# thinMan.net
KiCad netlist of a schematic drawn in EAGLE
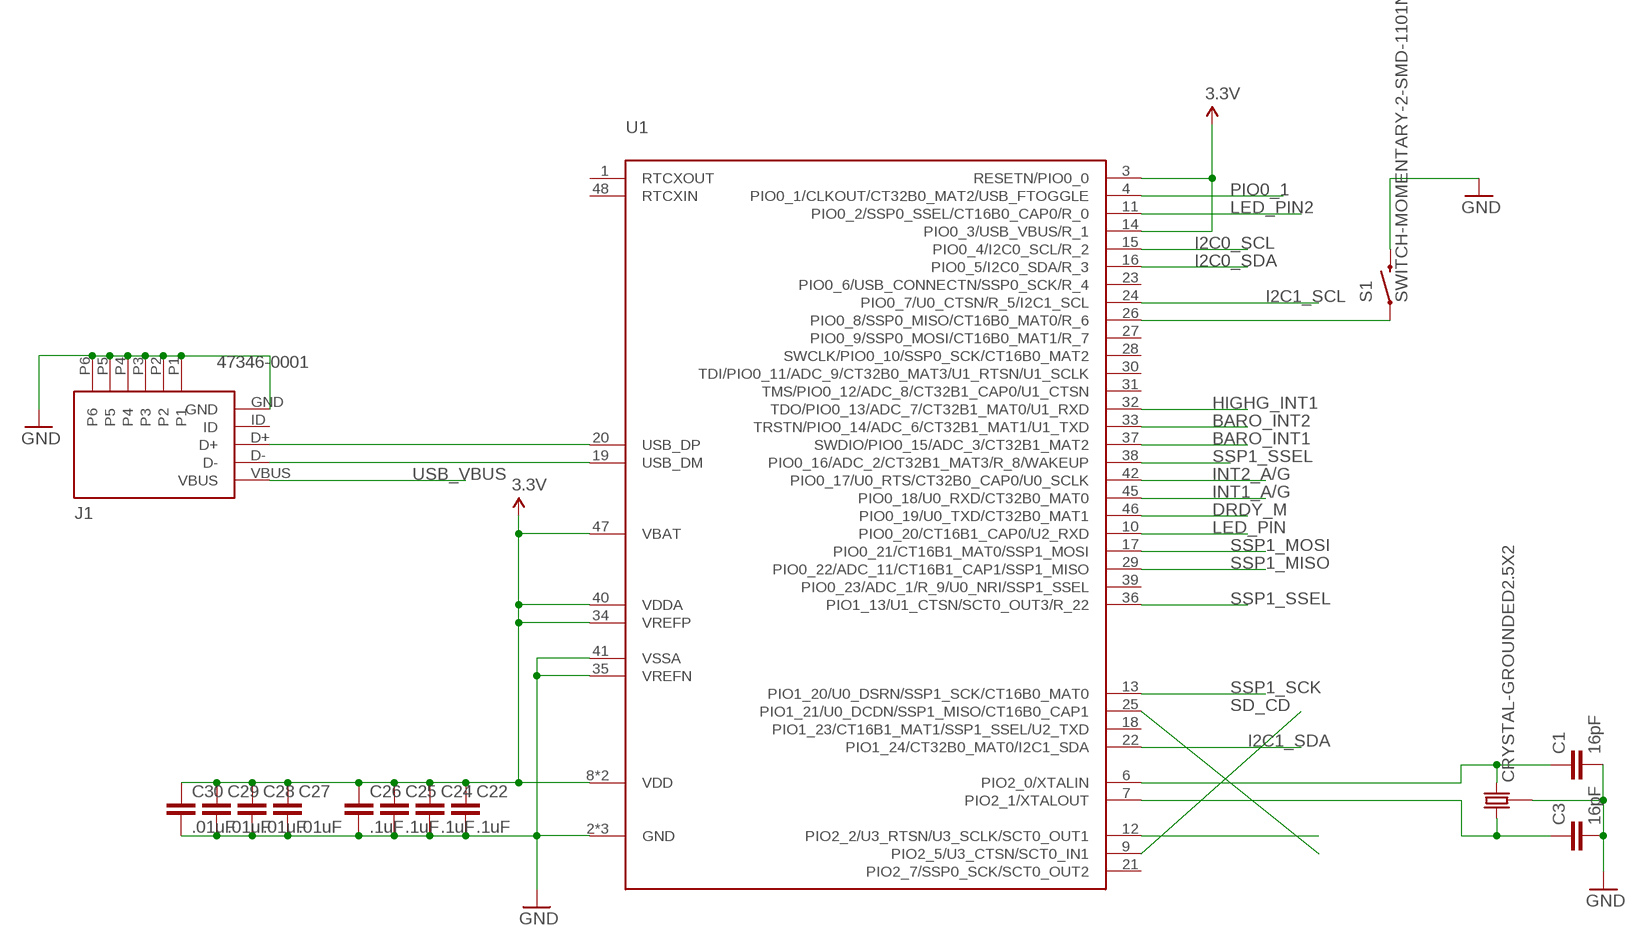
[diagram p0: schematic, sheet 1]
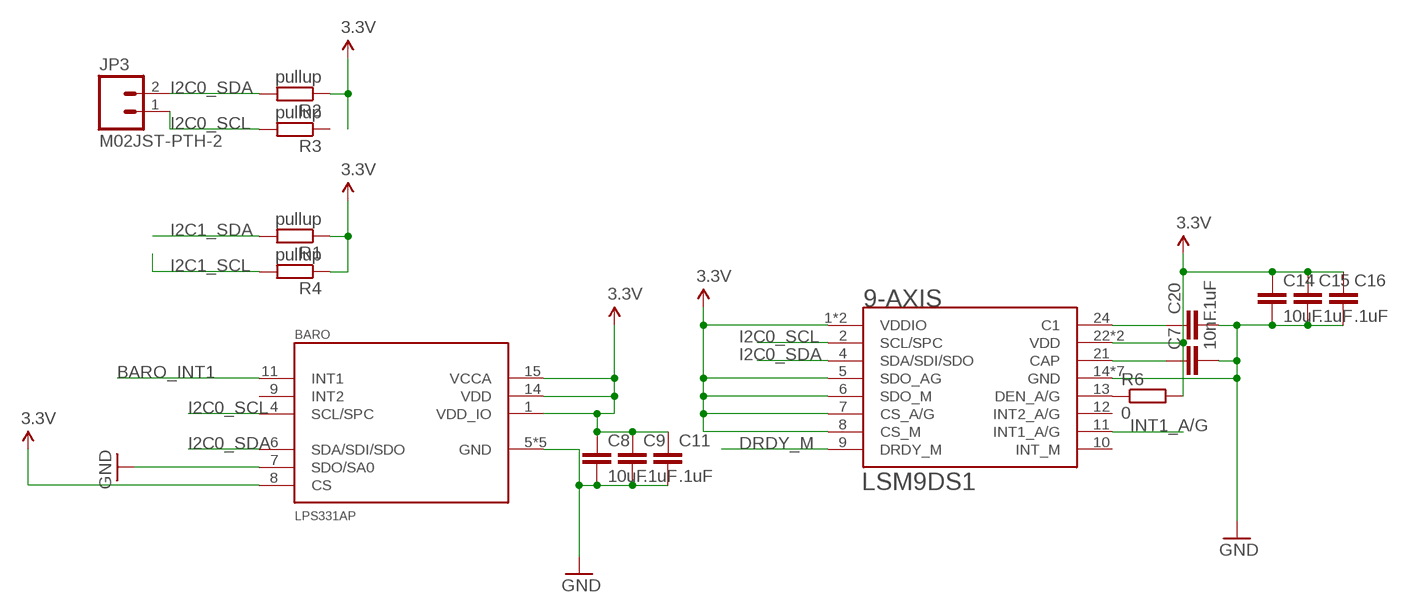
[diagram p1: schematic, sheet 2]
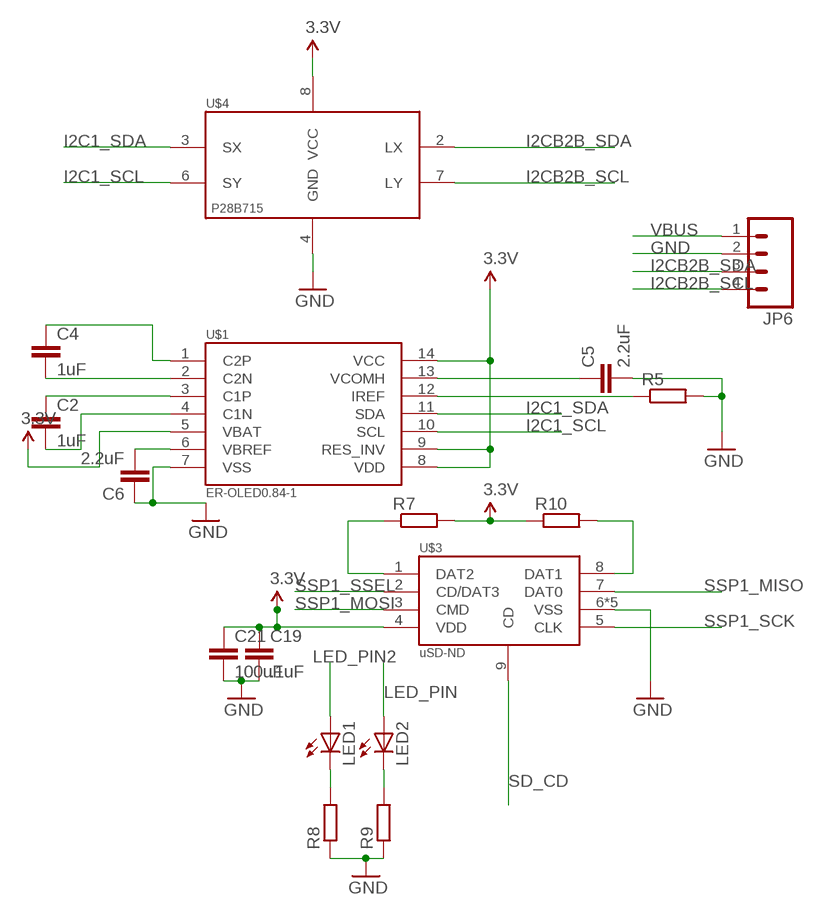
[diagram p2: schematic, sheet 3]
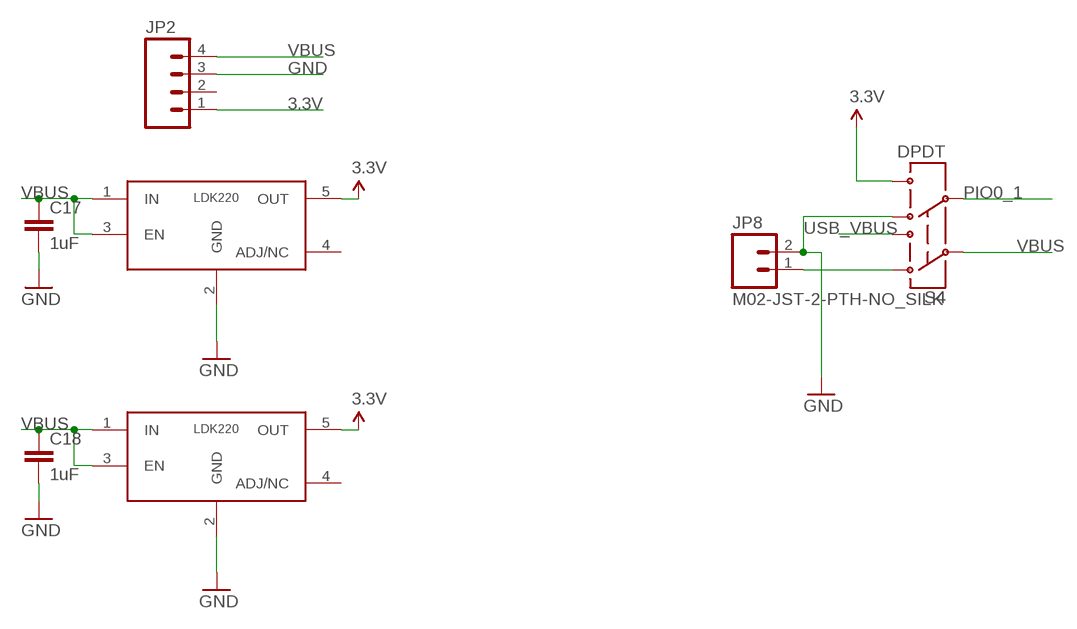
[diagram p3: schematic, sheet 4]

(export (version "E")
  (design (tool "Eeschema 10.0.6"))
  (components
    (comp (ref "C17")
      (value "1uF")
      (footprint "eagle-import:C0402")
      (libsource (lib "eagle-import") (part "C0402"))
    )
    (comp (ref "C18")
      (value "1uF")
      (footprint "eagle-import:C0402")
      (libsource (lib "eagle-import") (part "C0402"))
    )
    (comp (ref "JP2")
      (value "M04JST")
      (footprint "eagle-import:1X04-1.5MM_JST")
      (libsource (lib "eagle-import") (part "M04JST"))
    )
    (comp (ref "JP8")
      (value "M02-JST-2-PTH-NO_SILK")
      (footprint "eagle-import:JST-2-PTH-NS")
      (libsource (lib "eagle-import") (part "M02-JST-2-PTH-NO_SILK"))
    )
    (comp (ref "S4")
      (value "DPDT")
      (footprint "eagle-import:AYZ0202")
      (libsource (lib "eagle-import") (part "SWITCH-DPDTAYZ0202"))
    )
    (comp (ref "U$2")
      (value "LDK220M33R")
      (footprint "eagle-import:SOT23-5")
      (libsource (lib "eagle-import") (part "LDK220M33R"))
    )
    (comp (ref "U$6")
      (value "LDK220M33R")
      (footprint "eagle-import:SOT23-5")
      (libsource (lib "eagle-import") (part "LDK220M33R"))
    )
    (comp (ref "9-AXIS")
      (value "LSM9DS1")
      (footprint "eagle-import:LGA-24L-3.5X3X1")
      (libsource (lib "eagle-import") (part "LSM9DS1"))
    )
    (comp (ref "BARO")
      (value "LPS331AP")
      (footprint "eagle-import:LGA-16-3X3X1")
      (fields (field (name "MPN") "LPS331APTR"))
      (libsource (lib "eagle-import") (part "LPS331AP"))
    )
    (comp (ref "C7")
      (value "10nF")
      (footprint "eagle-import:C0402")
      (fields (field (name "MPN") "S103M47Z5UN63L0R"))
      (libsource (lib "eagle-import") (part "C0402"))
    )
    (comp (ref "C8")
      (value "10uF")
      (footprint "eagle-import:C0402")
      (libsource (lib "eagle-import") (part "C0402"))
    )
    (comp (ref "C9")
      (value ".1uF")
      (footprint "eagle-import:C0402")
      (libsource (lib "eagle-import") (part "C0402"))
    )
    (comp (ref "C11")
      (value ".1uF")
      (footprint "eagle-import:C0402")
      (libsource (lib "eagle-import") (part "C0402"))
    )
    (comp (ref "C14")
      (value "10uF")
      (footprint "eagle-import:C0402")
      (libsource (lib "eagle-import") (part "C0402"))
    )
    (comp (ref "C15")
      (value ".1uF")
      (footprint "eagle-import:C0402")
      (libsource (lib "eagle-import") (part "C0402"))
    )
    (comp (ref "C16")
      (value ".1uF")
      (footprint "eagle-import:C0402")
      (libsource (lib "eagle-import") (part "C0402"))
    )
    (comp (ref "C20")
      (value ".1uF")
      (footprint "eagle-import:C0402")
      (fields (field (name "MPN") "S103M47Z5UN63L0R"))
      (libsource (lib "eagle-import") (part "C0402"))
    )
    (comp (ref "JP3")
      (value "M02JST-PTH-2")
      (footprint "eagle-import:JST-2-PTH")
      (libsource (lib "eagle-import") (part "M02JST-PTH-2"))
    )
    (comp (ref "R1")
      (value "pullup")
      (footprint "eagle-import:R0805")
      (libsource (lib "eagle-import") (part "R0805"))
    )
    (comp (ref "R2")
      (value "pullup")
      (footprint "eagle-import:R0402")
      (libsource (lib "eagle-import") (part "R0402"))
    )
    (comp (ref "R3")
      (value "pullup")
      (footprint "eagle-import:R0402")
      (libsource (lib "eagle-import") (part "R0402"))
    )
    (comp (ref "R4")
      (value "pullup")
      (footprint "eagle-import:R0805")
      (libsource (lib "eagle-import") (part "R0805"))
    )
    (comp (ref "R6")
      (value "0")
      (footprint "eagle-import:R0402")
      (libsource (lib "eagle-import") (part "R0402"))
    )
    (comp (ref "C2")
      (value "1uF")
      (footprint "eagle-import:C0402")
      (fields (field (name "MPN") "MC0402X105M6R3CT"))
      (libsource (lib "eagle-import") (part "C0402"))
    )
    (comp (ref "C4")
      (value "1uF")
      (footprint "eagle-import:C0402")
      (fields (field (name "MPN") "MC0402X105M6R3CT"))
      (libsource (lib "eagle-import") (part "C0402"))
    )
    (comp (ref "C5")
      (value "2.2uF")
      (footprint "eagle-import:C0402")
      (fields (field (name "MPN") "C1005X6S0G225M050BC"))
      (libsource (lib "eagle-import") (part "C0402"))
    )
    (comp (ref "C6")
      (value "2.2uF")
      (footprint "eagle-import:C0402")
      (fields (field (name "MPN") "C1005X6S0G225M050BC"))
      (libsource (lib "eagle-import") (part "C0402"))
    )
    (comp (ref "C19")
      (value ".1uF")
      (footprint "eagle-import:C0402")
      (libsource (lib "eagle-import") (part "C0402"))
    )
    (comp (ref "C21")
      (value "100uF")
      (footprint "eagle-import:C1206")
      (libsource (lib "eagle-import") (part "CC1206"))
    )
    (comp (ref "JP6")
      (value "M04JST")
      (footprint "eagle-import:1X04-1.5MM_JST")
      (libsource (lib "eagle-import") (part "M04JST"))
    )
    (comp (ref "LED1")
      (value "LEDCHIPLED_0603")
      (footprint "eagle-import:CHIPLED_0603")
      (libsource (lib "eagle-import") (part "LEDCHIPLED_0603"))
    )
    (comp (ref "LED2")
      (value "LEDCHIPLED_0603")
      (footprint "eagle-import:CHIPLED_0603")
      (libsource (lib "eagle-import") (part "LEDCHIPLED_0603"))
    )
    (comp (ref "R5")
      (value "R0402")
      (footprint "eagle-import:R0402")
      (libsource (lib "eagle-import") (part "R0402"))
    )
    (comp (ref "R7")
      (value "R0402")
      (footprint "eagle-import:R0402")
      (libsource (lib "eagle-import") (part "R0402"))
    )
    (comp (ref "R8")
      (value "R0402")
      (footprint "eagle-import:R0402")
      (libsource (lib "eagle-import") (part "R0402"))
    )
    (comp (ref "R9")
      (value "R0402")
      (footprint "eagle-import:R0402")
      (libsource (lib "eagle-import") (part "R0402"))
    )
    (comp (ref "R10")
      (value "R0402")
      (footprint "eagle-import:R0402")
      (libsource (lib "eagle-import") (part "R0402"))
    )
    (comp (ref "U$1")
      (value "ER-OLED0.84-1")
      (footprint "eagle-import:MOLEX_52892-1433")
      (libsource (lib "eagle-import") (part "ER-OLED0.84-1"))
    )
    (comp (ref "U$3")
      (value "MICROSD-CD")
      (footprint "eagle-import:MOLEX_SD-47352-101")
      (libsource (lib "eagle-import") (part "MICROSD-CD"))
    )
    (comp (ref "U$4")
      (value "P82B715")
      (footprint "eagle-import:SO8")
      (libsource (lib "eagle-import") (part "P82B715"))
    )
    (comp (ref "C1")
      (value "16pF")
      (footprint "eagle-import:C0402")
      (libsource (lib "eagle-import") (part "C0402"))
    )
    (comp (ref "C3")
      (value "16pF")
      (footprint "eagle-import:C0402")
      (libsource (lib "eagle-import") (part "C0402"))
    )
    (comp (ref "C22")
      (value ".1uF")
      (footprint "eagle-import:C0402")
      (libsource (lib "eagle-import") (part "C0402"))
    )
    (comp (ref "C24")
      (value ".1uF")
      (footprint "eagle-import:C0402")
      (libsource (lib "eagle-import") (part "C0402"))
    )
    (comp (ref "C25")
      (value ".1uF")
      (footprint "eagle-import:C0402")
      (libsource (lib "eagle-import") (part "C0402"))
    )
    (comp (ref "C26")
      (value ".1uF")
      (footprint "eagle-import:C0402")
      (libsource (lib "eagle-import") (part "C0402"))
    )
    (comp (ref "C27")
      (value ".01uF")
      (footprint "eagle-import:C0402")
      (libsource (lib "eagle-import") (part "C0402"))
    )
    (comp (ref "C28")
      (value ".01uF")
      (footprint "eagle-import:C0402")
      (libsource (lib "eagle-import") (part "C0402"))
    )
    (comp (ref "C29")
      (value ".01uF")
      (footprint "eagle-import:C0402")
      (libsource (lib "eagle-import") (part "C0402"))
    )
    (comp (ref "C30")
      (value ".01uF")
      (footprint "eagle-import:C0402")
      (libsource (lib "eagle-import") (part "C0402"))
    )
    (comp (ref "J1")
      (value "47346-0001")
      (footprint "eagle-import:MICRO_USB")
      (fields (field (name "PARTNO") "AS-ITM-00021"))
      (libsource (lib "eagle-import") (part "MICRO-USB"))
    )
    (comp (ref "S1")
      (value "SWITCH-MOMENTARY-2-SMD-1101NE")
      (footprint "eagle-import:TACTILE-SWITCH-1101NE")
      (libsource (lib "eagle-import") (part "SWITCH-MOMENTARY-2-SMD-1101NE"))
    )
    (comp (ref "U$5")
      (value "CRYSTAL-GROUNDED2.5X2")
      (footprint "eagle-import:CRYSTAL-SMD-2.5X2")
      (libsource (lib "eagle-import") (part "CRYSTAL-GROUNDED2.5X2"))
    )
    (comp (ref "U1")
      (value "LPC11U68JBD48")
      (footprint "eagle-import:LQFP48")
      (libsource (lib "eagle-import") (part "LPC11U68JBD48"))
    )
  )
  (nets
    (net (code "1") (name "3.3V") (class "Default")
      (node (ref "9-AXIS") (pin "1") (pinfunction "VDDIO_1") (pintype "bidirectional"))
      (node (ref "9-AXIS") (pin "22") (pinfunction "VDD_22") (pintype "bidirectional"))
      (node (ref "9-AXIS") (pin "23") (pinfunction "VDD_23") (pintype "bidirectional"))
      (node (ref "9-AXIS") (pin "3") (pinfunction "VDDIO_3") (pintype "bidirectional"))
      (node (ref "9-AXIS") (pin "5") (pinfunction "SDO_AG_5") (pintype "bidirectional"))
      (node (ref "9-AXIS") (pin "6") (pinfunction "SDO_M_6") (pintype "bidirectional"))
      (node (ref "9-AXIS") (pin "7") (pinfunction "CS_A/G_7") (pintype "bidirectional"))
      (node (ref "9-AXIS") (pin "8") (pinfunction "CS_M_8") (pintype "bidirectional"))
      (node (ref "BARO") (pin "1") (pinfunction "VDD_IO_1") (pintype "bidirectional"))
      (node (ref "BARO") (pin "14") (pinfunction "VDD_14") (pintype "bidirectional"))
      (node (ref "BARO") (pin "15") (pinfunction "VCCA_15") (pintype "bidirectional"))
      (node (ref "BARO") (pin "8") (pinfunction "CS_8") (pintype "bidirectional"))
      (node (ref "C11") (pin "1") (pinfunction "1_1") (pintype "passive"))
      (node (ref "C14") (pin "1") (pinfunction "1_1") (pintype "passive"))
      (node (ref "C15") (pin "1") (pinfunction "1_1") (pintype "passive"))
      (node (ref "C16") (pin "1") (pinfunction "1_1") (pintype "passive"))
      (node (ref "C19") (pin "1") (pinfunction "1_1") (pintype "passive"))
      (node (ref "C21") (pin "1") (pinfunction "1_1") (pintype "passive"))
      (node (ref "C22") (pin "1") (pinfunction "1_1") (pintype "passive"))
      (node (ref "C24") (pin "1") (pinfunction "1_1") (pintype "passive"))
      (node (ref "C25") (pin "1") (pinfunction "1_1") (pintype "passive"))
      (node (ref "C26") (pin "1") (pinfunction "1_1") (pintype "passive"))
      (node (ref "C27") (pin "1") (pinfunction "1_1") (pintype "passive"))
      (node (ref "C28") (pin "1") (pinfunction "1_1") (pintype "passive"))
      (node (ref "C29") (pin "1") (pinfunction "1_1") (pintype "passive"))
      (node (ref "C30") (pin "1") (pinfunction "1_1") (pintype "passive"))
      (node (ref "C8") (pin "1") (pinfunction "1_1") (pintype "passive"))
      (node (ref "C9") (pin "1") (pinfunction "1_1") (pintype "passive"))
      (node (ref "JP2") (pin "1") (pinfunction "1_1") (pintype "passive"))
      (node (ref "R1") (pin "1") (pinfunction "1_1") (pintype "passive"))
      (node (ref "R10") (pin "1") (pinfunction "1_1") (pintype "passive"))
      (node (ref "R2") (pin "1") (pinfunction "1_1") (pintype "passive"))
      (node (ref "R4") (pin "1") (pinfunction "1_1") (pintype "passive"))
      (node (ref "R6") (pin "2") (pinfunction "2_2") (pintype "passive"))
      (node (ref "R7") (pin "2") (pinfunction "2_2") (pintype "passive"))
      (node (ref "S4") (pin "6") (pinfunction "6_6") (pintype "bidirectional"))
      (node (ref "U$1") (pin "14") (pinfunction "VCC_14") (pintype "bidirectional"))
      (node (ref "U$1") (pin "5") (pinfunction "VBAT_5") (pintype "bidirectional"))
      (node (ref "U$1") (pin "8") (pinfunction "VDD_8") (pintype "bidirectional"))
      (node (ref "U$1") (pin "9") (pinfunction "RES_INV_9") (pintype "bidirectional"))
      (node (ref "U$2") (pin "5") (pinfunction "OUT_5") (pintype "bidirectional"))
      (node (ref "U$3") (pin "4") (pinfunction "VDD_4") (pintype "bidirectional"))
      (node (ref "U$4") (pin "8") (pinfunction "VCC_8") (pintype "bidirectional"))
      (node (ref "U$6") (pin "5") (pinfunction "OUT_5") (pintype "bidirectional"))
      (node (ref "U1") (pin "14") (pinfunction "PIO0_3/USB_VBUS/R_1_14") (pintype "bidirectional"))
      (node (ref "U1") (pin "3") (pinfunction "RESETN/PIO0_0_3") (pintype "bidirectional"))
      (node (ref "U1") (pin "34") (pinfunction "VREFP_34") (pintype "bidirectional"))
      (node (ref "U1") (pin "40") (pinfunction "VDDA_40") (pintype "bidirectional"))
      (node (ref "U1") (pin "44") (pinfunction "VDD_44") (pintype "bidirectional"))
      (node (ref "U1") (pin "47") (pinfunction "VBAT_47") (pintype "bidirectional"))
      (node (ref "U1") (pin "8") (pinfunction "VDD_8") (pintype "bidirectional"))
    )
    (net (code "2") (name "BARO_INT1") (class "Default")
      (node (ref "BARO") (pin "11") (pinfunction "INT1_11") (pintype "bidirectional"))
      (node (ref "U1") (pin "37") (pinfunction "SWDIO/PIO0_15/ADC_3/CT32B1_MAT2_37") (pintype "bidirectional"))
    )
    (net (code "3") (name "BARO_INT2") (class "Default")
      (node (ref "U1") (pin "33") (pinfunction "TRSTN/PIO0_14/ADC_6/CT32B1_MAT1/U1_TXD_33") (pintype "bidirectional"))
    )
    (net (code "4") (name "DRDY_M") (class "Default")
      (node (ref "9-AXIS") (pin "9") (pinfunction "DRDY_M_9") (pintype "bidirectional"))
      (node (ref "U1") (pin "46") (pinfunction "PIO0_19/U0_TXD/CT32B0_MAT1_46") (pintype "bidirectional"))
    )
    (net (code "5") (name "GND") (class "Default")
      (node (ref "9-AXIS") (pin "14") (pinfunction "GND_14") (pintype "bidirectional"))
      (node (ref "9-AXIS") (pin "15") (pinfunction "GND_15") (pintype "bidirectional"))
      (node (ref "9-AXIS") (pin "16") (pinfunction "GND_16") (pintype "bidirectional"))
      (node (ref "9-AXIS") (pin "17") (pinfunction "GND_17") (pintype "bidirectional"))
      (node (ref "9-AXIS") (pin "18") (pinfunction "GND_18") (pintype "bidirectional"))
      (node (ref "9-AXIS") (pin "19") (pinfunction "GND_19") (pintype "bidirectional"))
      (node (ref "9-AXIS") (pin "20") (pinfunction "GND_20") (pintype "bidirectional"))
      (node (ref "BARO") (pin "10") (pinfunction "GND_10") (pintype "bidirectional"))
      (node (ref "BARO") (pin "12") (pinfunction "GND_12") (pintype "bidirectional"))
      (node (ref "BARO") (pin "13") (pinfunction "GND_13") (pintype "bidirectional"))
      (node (ref "BARO") (pin "16") (pinfunction "GND_16") (pintype "bidirectional"))
      (node (ref "BARO") (pin "5") (pinfunction "GND_5") (pintype "bidirectional"))
      (node (ref "BARO") (pin "7") (pinfunction "SDO/SA0_7") (pintype "bidirectional"))
      (node (ref "C1") (pin "2") (pinfunction "2_2") (pintype "passive"))
      (node (ref "C11") (pin "2") (pinfunction "2_2") (pintype "passive"))
      (node (ref "C14") (pin "2") (pinfunction "2_2") (pintype "passive"))
      (node (ref "C15") (pin "2") (pinfunction "2_2") (pintype "passive"))
      (node (ref "C16") (pin "2") (pinfunction "2_2") (pintype "passive"))
      (node (ref "C17") (pin "2") (pinfunction "2_2") (pintype "passive"))
      (node (ref "C18") (pin "2") (pinfunction "2_2") (pintype "passive"))
      (node (ref "C19") (pin "2") (pinfunction "2_2") (pintype "passive"))
      (node (ref "C20") (pin "2") (pinfunction "2_2") (pintype "passive"))
      (node (ref "C21") (pin "2") (pinfunction "2_2") (pintype "passive"))
      (node (ref "C22") (pin "2") (pinfunction "2_2") (pintype "passive"))
      (node (ref "C24") (pin "2") (pinfunction "2_2") (pintype "passive"))
      (node (ref "C25") (pin "2") (pinfunction "2_2") (pintype "passive"))
      (node (ref "C26") (pin "2") (pinfunction "2_2") (pintype "passive"))
      (node (ref "C27") (pin "2") (pinfunction "2_2") (pintype "passive"))
      (node (ref "C28") (pin "2") (pinfunction "2_2") (pintype "passive"))
      (node (ref "C29") (pin "2") (pinfunction "2_2") (pintype "passive"))
      (node (ref "C3") (pin "2") (pinfunction "2_2") (pintype "passive"))
      (node (ref "C30") (pin "2") (pinfunction "2_2") (pintype "passive"))
      (node (ref "C5") (pin "2") (pinfunction "2_2") (pintype "passive"))
      (node (ref "C6") (pin "1") (pinfunction "1_1") (pintype "passive"))
      (node (ref "C7") (pin "2") (pinfunction "2_2") (pintype "passive"))
      (node (ref "C8") (pin "2") (pinfunction "2_2") (pintype "passive"))
      (node (ref "C9") (pin "2") (pinfunction "2_2") (pintype "passive"))
      (node (ref "J1") (pin "GND") (pinfunction "GND_GND") (pintype "bidirectional"))
      (node (ref "J1") (pin "P1") (pinfunction "P1_P1") (pintype "bidirectional"))
      (node (ref "J1") (pin "P2") (pinfunction "P2_P2") (pintype "bidirectional"))
      (node (ref "J1") (pin "P3") (pinfunction "P3_P3") (pintype "bidirectional"))
      (node (ref "J1") (pin "P4") (pinfunction "P4_P4") (pintype "bidirectional"))
      (node (ref "J1") (pin "P5") (pinfunction "P5_P5") (pintype "bidirectional"))
      (node (ref "J1") (pin "P6") (pinfunction "P6_P6") (pintype "bidirectional"))
      (node (ref "JP2") (pin "3") (pinfunction "3_3") (pintype "passive"))
      (node (ref "JP6") (pin "2") (pinfunction "2_2") (pintype "passive"))
      (node (ref "JP8") (pin "2") (pinfunction "2_2") (pintype "passive"))
      (node (ref "R5") (pin "2") (pinfunction "2_2") (pintype "passive"))
      (node (ref "R8") (pin "1") (pinfunction "1_1") (pintype "passive"))
      (node (ref "R9") (pin "1") (pinfunction "1_1") (pintype "passive"))
      (node (ref "S1") (pin "2") (pinfunction "2_2") (pintype "passive"))
      (node (ref "S4") (pin "4") (pinfunction "4_4") (pintype "bidirectional"))
      (node (ref "U$1") (pin "7") (pinfunction "VSS_7") (pintype "bidirectional"))
      (node (ref "U$2") (pin "2") (pinfunction "GND_2") (pintype "bidirectional"))
      (node (ref "U$3") (pin "6") (pinfunction "VSS_6") (pintype "bidirectional"))
      (node (ref "U$3") (pin "G1") (pinfunction "VSS_G1") (pintype "bidirectional"))
      (node (ref "U$3") (pin "G2") (pinfunction "VSS_G2") (pintype "bidirectional"))
      (node (ref "U$3") (pin "G3") (pinfunction "VSS_G3") (pintype "bidirectional"))
      (node (ref "U$3") (pin "G4") (pinfunction "VSS_G4") (pintype "bidirectional"))
      (node (ref "U$4") (pin "4") (pinfunction "GND_4") (pintype "bidirectional"))
      (node (ref "U$5") (pin "GND1") (pinfunction "3_GND1") (pintype "passive"))
      (node (ref "U$5") (pin "GND2") (pinfunction "3_GND2") (pintype "passive"))
      (node (ref "U$6") (pin "2") (pinfunction "GND_2") (pintype "bidirectional"))
      (node (ref "U1") (pin "2") (pinfunction "GND_2") (pintype "bidirectional"))
      (node (ref "U1") (pin "35") (pinfunction "VREFN_35") (pintype "bidirectional"))
      (node (ref "U1") (pin "41") (pinfunction "VSSA_41") (pintype "bidirectional"))
      (node (ref "U1") (pin "43") (pinfunction "GND_43") (pintype "bidirectional"))
      (node (ref "U1") (pin "5") (pinfunction "GND_5") (pintype "bidirectional"))
    )
    (net (code "6") (name "HIGHG_INT1") (class "Default")
      (node (ref "U1") (pin "32") (pinfunction "TDO/PIO0_13/ADC_7/CT32B1_MAT0/U1_RXD_32") (pintype "bidirectional"))
    )
    (net (code "7") (name "I2C0_SCL") (class "Default")
      (node (ref "9-AXIS") (pin "2") (pinfunction "SCL/SPC_2") (pintype "bidirectional"))
      (node (ref "BARO") (pin "4") (pinfunction "SCL/SPC_4") (pintype "bidirectional"))
      (node (ref "JP3") (pin "1") (pinfunction "1_1") (pintype "passive"))
      (node (ref "R3") (pin "2") (pinfunction "2_2") (pintype "passive"))
      (node (ref "U1") (pin "15") (pinfunction "PIO0_4/I2C0_SCL/R_2_15") (pintype "bidirectional"))
    )
    (net (code "8") (name "I2C0_SDA") (class "Default")
      (node (ref "9-AXIS") (pin "4") (pinfunction "SDA/SDI/SDO_4") (pintype "bidirectional"))
      (node (ref "BARO") (pin "6") (pinfunction "SDA/SDI/SDO_6") (pintype "bidirectional"))
      (node (ref "JP3") (pin "2") (pinfunction "2_2") (pintype "passive"))
      (node (ref "R2") (pin "2") (pinfunction "2_2") (pintype "passive"))
      (node (ref "U1") (pin "16") (pinfunction "PIO0_5/I2C0_SDA/R_3_16") (pintype "bidirectional"))
    )
    (net (code "9") (name "I2C1_SCL") (class "Default")
      (node (ref "R4") (pin "2") (pinfunction "2_2") (pintype "passive"))
      (node (ref "U$1") (pin "10") (pinfunction "SCL_10") (pintype "bidirectional"))
      (node (ref "U$4") (pin "6") (pinfunction "SY_6") (pintype "bidirectional"))
      (node (ref "U1") (pin "24") (pinfunction "PIO0_7/U0_CTSN/R_5/I2C1_SCL_24") (pintype "bidirectional"))
    )
    (net (code "10") (name "I2C1_SDA") (class "Default")
      (node (ref "R1") (pin "2") (pinfunction "2_2") (pintype "passive"))
      (node (ref "U$1") (pin "11") (pinfunction "SDA_11") (pintype "bidirectional"))
      (node (ref "U$4") (pin "3") (pinfunction "SX_3") (pintype "bidirectional"))
      (node (ref "U1") (pin "22") (pinfunction "PIO1_24/CT32B0_MAT0/I2C1_SDA_22") (pintype "bidirectional"))
    )
    (net (code "11") (name "I2CB2B_SCL") (class "Default")
      (node (ref "JP6") (pin "4") (pinfunction "4_4") (pintype "passive"))
      (node (ref "U$4") (pin "7") (pinfunction "LY_7") (pintype "bidirectional"))
    )
    (net (code "12") (name "I2CB2B_SDA") (class "Default")
      (node (ref "JP6") (pin "3") (pinfunction "3_3") (pintype "passive"))
      (node (ref "U$4") (pin "2") (pinfunction "LX_2") (pintype "bidirectional"))
    )
    (net (code "13") (name "INT1_A{slash}G") (class "Default")
      (node (ref "9-AXIS") (pin "11") (pinfunction "INT1_A/G_11") (pintype "bidirectional"))
      (node (ref "U1") (pin "45") (pinfunction "PIO0_18/U0_RXD/CT32B0_MAT0_45") (pintype "bidirectional"))
    )
    (net (code "14") (name "INT2_A{slash}G") (class "Default")
      (node (ref "U1") (pin "42") (pinfunction "PIO0_17/U0_RTS/CT32B0_CAP0/U0_SCLK_42") (pintype "bidirectional"))
    )
    (net (code "15") (name "LED_PIN") (class "Default")
      (node (ref "LED2") (pin "A") (pinfunction "A_A") (pintype "passive"))
      (node (ref "U1") (pin "10") (pinfunction "PIO0_20/CT16B1_CAP0/U2_RXD_10") (pintype "bidirectional"))
    )
    (net (code "16") (name "LED_PIN2") (class "Default")
      (node (ref "LED1") (pin "A") (pinfunction "A_A") (pintype "passive"))
      (node (ref "U1") (pin "11") (pinfunction "PIO0_2/SSP0_SSEL/CT16B0_CAP0/R_0_11") (pintype "bidirectional"))
    )
    (net (code "17") (name "Net-(9-AXIS-C1)") (class "Default")
      (node (ref "9-AXIS") (pin "24") (pinfunction "C1_24") (pintype "bidirectional"))
      (node (ref "C20") (pin "1") (pinfunction "1_1") (pintype "passive"))
    )
    (net (code "18") (name "Net-(9-AXIS-CAP)") (class "Default")
      (node (ref "9-AXIS") (pin "21") (pinfunction "CAP_21") (pintype "bidirectional"))
      (node (ref "C7") (pin "1") (pinfunction "1_1") (pintype "passive"))
    )
    (net (code "19") (name "Net-(9-AXIS-DEN_A{slash}G)") (class "Default")
      (node (ref "9-AXIS") (pin "13") (pinfunction "DEN_A/G_13") (pintype "bidirectional"))
      (node (ref "R6") (pin "1") (pinfunction "1_1") (pintype "passive"))
    )
    (net (code "20") (name "Net-(JP8-Pad1)") (class "Default")
      (node (ref "JP8") (pin "1") (pinfunction "1_1") (pintype "passive"))
      (node (ref "S4") (pin "1") (pinfunction "1_1") (pintype "bidirectional"))
    )
    (net (code "21") (name "Net-(LED1-PadC)") (class "Default")
      (node (ref "LED1") (pin "C") (pinfunction "C_C") (pintype "passive"))
      (node (ref "R8") (pin "2") (pinfunction "2_2") (pintype "passive"))
    )
    (net (code "22") (name "Net-(LED2-PadC)") (class "Default")
      (node (ref "LED2") (pin "C") (pinfunction "C_C") (pintype "passive"))
      (node (ref "R9") (pin "2") (pinfunction "2_2") (pintype "passive"))
    )
    (net (code "23") (name "Net-(U$1-C1N)") (class "Default")
      (node (ref "C2") (pin "2") (pinfunction "2_2") (pintype "passive"))
      (node (ref "U$1") (pin "4") (pinfunction "C1N_4") (pintype "bidirectional"))
    )
    (net (code "24") (name "Net-(U$1-C1P)") (class "Default")
      (node (ref "C2") (pin "1") (pinfunction "1_1") (pintype "passive"))
      (node (ref "U$1") (pin "3") (pinfunction "C1P_3") (pintype "bidirectional"))
    )
    (net (code "25") (name "Net-(U$1-C2N)") (class "Default")
      (node (ref "C4") (pin "2") (pinfunction "2_2") (pintype "passive"))
      (node (ref "U$1") (pin "2") (pinfunction "C2N_2") (pintype "bidirectional"))
    )
    (net (code "26") (name "Net-(U$1-C2P)") (class "Default")
      (node (ref "C4") (pin "1") (pinfunction "1_1") (pintype "passive"))
      (node (ref "U$1") (pin "1") (pinfunction "C2P_1") (pintype "bidirectional"))
    )
    (net (code "27") (name "Net-(U$1-IREF)") (class "Default")
      (node (ref "R5") (pin "1") (pinfunction "1_1") (pintype "passive"))
      (node (ref "U$1") (pin "12") (pinfunction "IREF_12") (pintype "bidirectional"))
    )
    (net (code "28") (name "Net-(U$1-VBREF)") (class "Default")
      (node (ref "C6") (pin "2") (pinfunction "2_2") (pintype "passive"))
      (node (ref "U$1") (pin "6") (pinfunction "VBREF_6") (pintype "bidirectional"))
    )
    (net (code "29") (name "Net-(U$1-VCOMH)") (class "Default")
      (node (ref "C5") (pin "1") (pinfunction "1_1") (pintype "passive"))
      (node (ref "U$1") (pin "13") (pinfunction "VCOMH_13") (pintype "bidirectional"))
    )
    (net (code "30") (name "Net-(U$3-DAT1)") (class "Default")
      (node (ref "R10") (pin "2") (pinfunction "2_2") (pintype "passive"))
      (node (ref "U$3") (pin "8") (pinfunction "DAT1_8") (pintype "bidirectional"))
    )
    (net (code "31") (name "Net-(U$3-DAT2)") (class "Default")
      (node (ref "R7") (pin "1") (pinfunction "1_1") (pintype "passive"))
      (node (ref "U$3") (pin "1") (pinfunction "DAT2_1") (pintype "bidirectional"))
    )
    (net (code "32") (name "Net-(U$5-1)") (class "Default")
      (node (ref "C3") (pin "1") (pinfunction "1_1") (pintype "passive"))
      (node (ref "U$5") (pin "P1") (pinfunction "1_P1") (pintype "passive"))
      (node (ref "U1") (pin "7") (pinfunction "PIO2_1/XTALOUT_7") (pintype "bidirectional"))
    )
    (net (code "33") (name "Net-(U$5-2)") (class "Default")
      (node (ref "C1") (pin "1") (pinfunction "1_1") (pintype "passive"))
      (node (ref "U$5") (pin "P2") (pinfunction "2_P2") (pintype "passive"))
      (node (ref "U1") (pin "6") (pinfunction "PIO2_0/XTALIN_6") (pintype "bidirectional"))
    )
    (net (code "34") (name "Net-(U1-PIO0_8{slash}SSP0_MISO{slash}CT16B0_MAT0{slash}R_6)") (class "Default")
      (node (ref "S1") (pin "1") (pinfunction "1_1") (pintype "passive"))
      (node (ref "U1") (pin "26") (pinfunction "PIO0_8/SSP0_MISO/CT16B0_MAT0/R_6_26") (pintype "bidirectional"))
    )
    (net (code "35") (name "Net-(U1-USB_DM)") (class "Default")
      (node (ref "J1") (pin "D-") (pinfunction "D-_D-") (pintype "bidirectional"))
      (node (ref "U1") (pin "19") (pinfunction "USB_DM_19") (pintype "bidirectional"))
    )
    (net (code "36") (name "Net-(U1-USB_DP)") (class "Default")
      (node (ref "J1") (pin "D+") (pinfunction "D+_D+") (pintype "bidirectional"))
      (node (ref "U1") (pin "20") (pinfunction "USB_DP_20") (pintype "bidirectional"))
    )
    (net (code "37") (name "PIO0_1") (class "Default")
      (node (ref "S4") (pin "5") (pinfunction "5_5") (pintype "bidirectional"))
      (node (ref "U1") (pin "4") (pinfunction "PIO0_1/CLKOUT/CT32B0_MAT2/USB_FTOGGLE_4") (pintype "bidirectional"))
    )
    (net (code "38") (name "SD_CD") (class "Default")
      (node (ref "U$3") (pin "9") (pinfunction "CD_9") (pintype "bidirectional"))
      (node (ref "U1") (pin "9") (pinfunction "PIO2_5/U3_CTSN/SCT0_IN1_9") (pintype "bidirectional"))
    )
    (net (code "39") (name "SSP1_MISO") (class "Default")
      (node (ref "U$3") (pin "7") (pinfunction "DAT0_7") (pintype "bidirectional"))
      (node (ref "U1") (pin "29") (pinfunction "PIO0_22/ADC_11/CT16B1_CAP1/SSP1_MISO_29") (pintype "bidirectional"))
    )
    (net (code "40") (name "SSP1_MOSI") (class "Default")
      (node (ref "U$3") (pin "3") (pinfunction "CMD_3") (pintype "bidirectional"))
      (node (ref "U1") (pin "17") (pinfunction "PIO0_21/CT16B1_MAT0/SSP1_MOSI_17") (pintype "bidirectional"))
    )
    (net (code "41") (name "SSP1_SCK") (class "Default")
      (node (ref "U$3") (pin "5") (pinfunction "CLK_5") (pintype "bidirectional"))
      (node (ref "U1") (pin "13") (pinfunction "PIO1_20/U0_DSRN/SSP1_SCK/CT16B0_MAT0_13") (pintype "bidirectional"))
    )
    (net (code "42") (name "SSP1_SSEL") (class "Default")
      (node (ref "U$3") (pin "2") (pinfunction "CD/DAT3_2") (pintype "bidirectional"))
      (node (ref "U1") (pin "38") (pinfunction "PIO0_16/ADC_2/CT32B1_MAT3/R_8/WAKEUP_38") (pintype "bidirectional"))
    )
    (net (code "43") (name "USB_VBUS") (class "Default")
      (node (ref "J1") (pin "VBUS") (pinfunction "VBUS_VBUS") (pintype "bidirectional"))
      (node (ref "S4") (pin "3") (pinfunction "3_3") (pintype "bidirectional"))
    )
    (net (code "44") (name "VBUS") (class "Default")
      (node (ref "C17") (pin "1") (pinfunction "1_1") (pintype "passive"))
      (node (ref "C18") (pin "1") (pinfunction "1_1") (pintype "passive"))
      (node (ref "JP2") (pin "4") (pinfunction "4_4") (pintype "passive"))
      (node (ref "JP6") (pin "1") (pinfunction "1_1") (pintype "passive"))
      (node (ref "S4") (pin "2") (pinfunction "2_2") (pintype "bidirectional"))
      (node (ref "U$2") (pin "1") (pinfunction "IN_1") (pintype "bidirectional"))
      (node (ref "U$2") (pin "3") (pinfunction "EN_3") (pintype "bidirectional"))
      (node (ref "U$6") (pin "1") (pinfunction "IN_1") (pintype "bidirectional"))
      (node (ref "U$6") (pin "3") (pinfunction "EN_3") (pintype "bidirectional"))
    )
    (net (code "45") (name "unconnected-(9-AXIS-INT2_A{slash}G-Pad12)") (class "Default")
      (node (ref "9-AXIS") (pin "12") (pinfunction "INT2_A/G_12") (pintype "bidirectional"))
    )
    (net (code "46") (name "unconnected-(9-AXIS-INT_M-Pad10)") (class "Default")
      (node (ref "9-AXIS") (pin "10") (pinfunction "INT_M_10") (pintype "bidirectional"))
    )
    (net (code "47") (name "unconnected-(BARO-INT2-Pad9)") (class "Default")
      (node (ref "BARO") (pin "9") (pinfunction "INT2_9") (pintype "bidirectional"))
    )
    (net (code "48") (name "unconnected-(J1-PadID)") (class "Default")
      (node (ref "J1") (pin "ID") (pinfunction "ID_ID") (pintype "bidirectional"))
    )
    (net (code "49") (name "unconnected-(JP2-Pad2)") (class "Default")
      (node (ref "JP2") (pin "2") (pinfunction "2_2") (pintype "passive"))
    )
    (net (code "50") (name "unconnected-(R3-Pad1)") (class "Default")
      (node (ref "R3") (pin "1") (pinfunction "1_1") (pintype "passive"))
    )
    (net (code "51") (name "unconnected-(U$2-ADJ{slash}NC-Pad4)") (class "Default")
      (node (ref "U$2") (pin "4") (pinfunction "ADJ/NC_4") (pintype "bidirectional"))
    )
    (net (code "52") (name "unconnected-(U$6-ADJ{slash}NC-Pad4)") (class "Default")
      (node (ref "U$6") (pin "4") (pinfunction "ADJ/NC_4") (pintype "bidirectional"))
    )
    (net (code "53") (name "unconnected-(U1-PIO0_6{slash}USB_CONNECTN{slash}SSP0_SCK{slash}R_4-Pad23)") (class "Default")
      (node (ref "U1") (pin "23") (pinfunction "PIO0_6/USB_CONNECTN/SSP0_SCK/R_4_23") (pintype "bidirectional"))
    )
    (net (code "54") (name "unconnected-(U1-PIO0_9{slash}SSP0_MOSI{slash}CT16B0_MAT1{slash}R_7-Pad27)") (class "Default")
      (node (ref "U1") (pin "27") (pinfunction "PIO0_9/SSP0_MOSI/CT16B0_MAT1/R_7_27") (pintype "bidirectional"))
    )
    (net (code "55") (name "unconnected-(U1-PIO0_23{slash}ADC_1{slash}R_9{slash}U0_NRI{slash}SSP1_SSEL-Pad39)") (class "Default")
      (node (ref "U1") (pin "39") (pinfunction "PIO0_23/ADC_1/R_9/U0_NRI/SSP1_SSEL_39") (pintype "bidirectional"))
    )
    (net (code "56") (name "unconnected-(U1-PIO1_13{slash}U1_CTSN{slash}SCT0_OUT3{slash}R_22-Pad36)") (class "Default")
      (node (ref "U1") (pin "36") (pinfunction "PIO1_13/U1_CTSN/SCT0_OUT3/R_22_36") (pintype "bidirectional"))
    )
    (net (code "57") (name "unconnected-(U1-PIO1_21{slash}U0_DCDN{slash}SSP1_MISO{slash}CT16B0_CAP1-Pad25)") (class "Default")
      (node (ref "U1") (pin "25") (pinfunction "PIO1_21/U0_DCDN/SSP1_MISO/CT16B0_CAP1_25") (pintype "bidirectional"))
    )
    (net (code "58") (name "unconnected-(U1-PIO1_23{slash}CT16B1_MAT1{slash}SSP1_SSEL{slash}U2_TXD-Pad18)") (class "Default")
      (node (ref "U1") (pin "18") (pinfunction "PIO1_23/CT16B1_MAT1/SSP1_SSEL/U2_TXD_18") (pintype "bidirectional"))
    )
    (net (code "59") (name "unconnected-(U1-PIO2_2{slash}U3_RTSN{slash}U3_SCLK{slash}SCT0_OUT1-Pad12)") (class "Default")
      (node (ref "U1") (pin "12") (pinfunction "PIO2_2/U3_RTSN/U3_SCLK/SCT0_OUT1_12") (pintype "bidirectional"))
    )
    (net (code "60") (name "unconnected-(U1-PIO2_7{slash}SSP0_SCK{slash}SCT0_OUT2-Pad21)") (class "Default")
      (node (ref "U1") (pin "21") (pinfunction "PIO2_7/SSP0_SCK/SCT0_OUT2_21") (pintype "bidirectional"))
    )
    (net (code "61") (name "unconnected-(U1-RTCXIN-Pad48)") (class "Default")
      (node (ref "U1") (pin "48") (pinfunction "RTCXIN_48") (pintype "bidirectional"))
    )
    (net (code "62") (name "unconnected-(U1-RTCXOUT-Pad1)") (class "Default")
      (node (ref "U1") (pin "1") (pinfunction "RTCXOUT_1") (pintype "bidirectional"))
    )
    (net (code "63") (name "unconnected-(U1-SWCLK{slash}PIO0_10{slash}SSP0_SCK{slash}CT16B0_MAT2-Pad28)") (class "Default")
      (node (ref "U1") (pin "28") (pinfunction "SWCLK/PIO0_10/SSP0_SCK/CT16B0_MAT2_28") (pintype "bidirectional"))
    )
    (net (code "64") (name "unconnected-(U1-TDI{slash}PIO0_11{slash}ADC_9{slash}CT32B0_MAT3{slash}U1_RTSN{slash}U1_SCLK-Pad30)") (class "Default")
      (node (ref "U1") (pin "30") (pinfunction "TDI/PIO0_11/ADC_9/CT32B0_MAT3/U1_RTSN/U1_SCLK_30") (pintype "bidirectional"))
    )
    (net (code "65") (name "unconnected-(U1-TMS{slash}PIO0_12{slash}ADC_8{slash}CT32B1_CAP0{slash}U1_CTSN-Pad31)") (class "Default")
      (node (ref "U1") (pin "31") (pinfunction "TMS/PIO0_12/ADC_8/CT32B1_CAP0/U1_CTSN_31") (pintype "bidirectional"))
    )
  )
)
